# be_mdv.net
KiCad netlist of a schematic drawn in Altium Designer
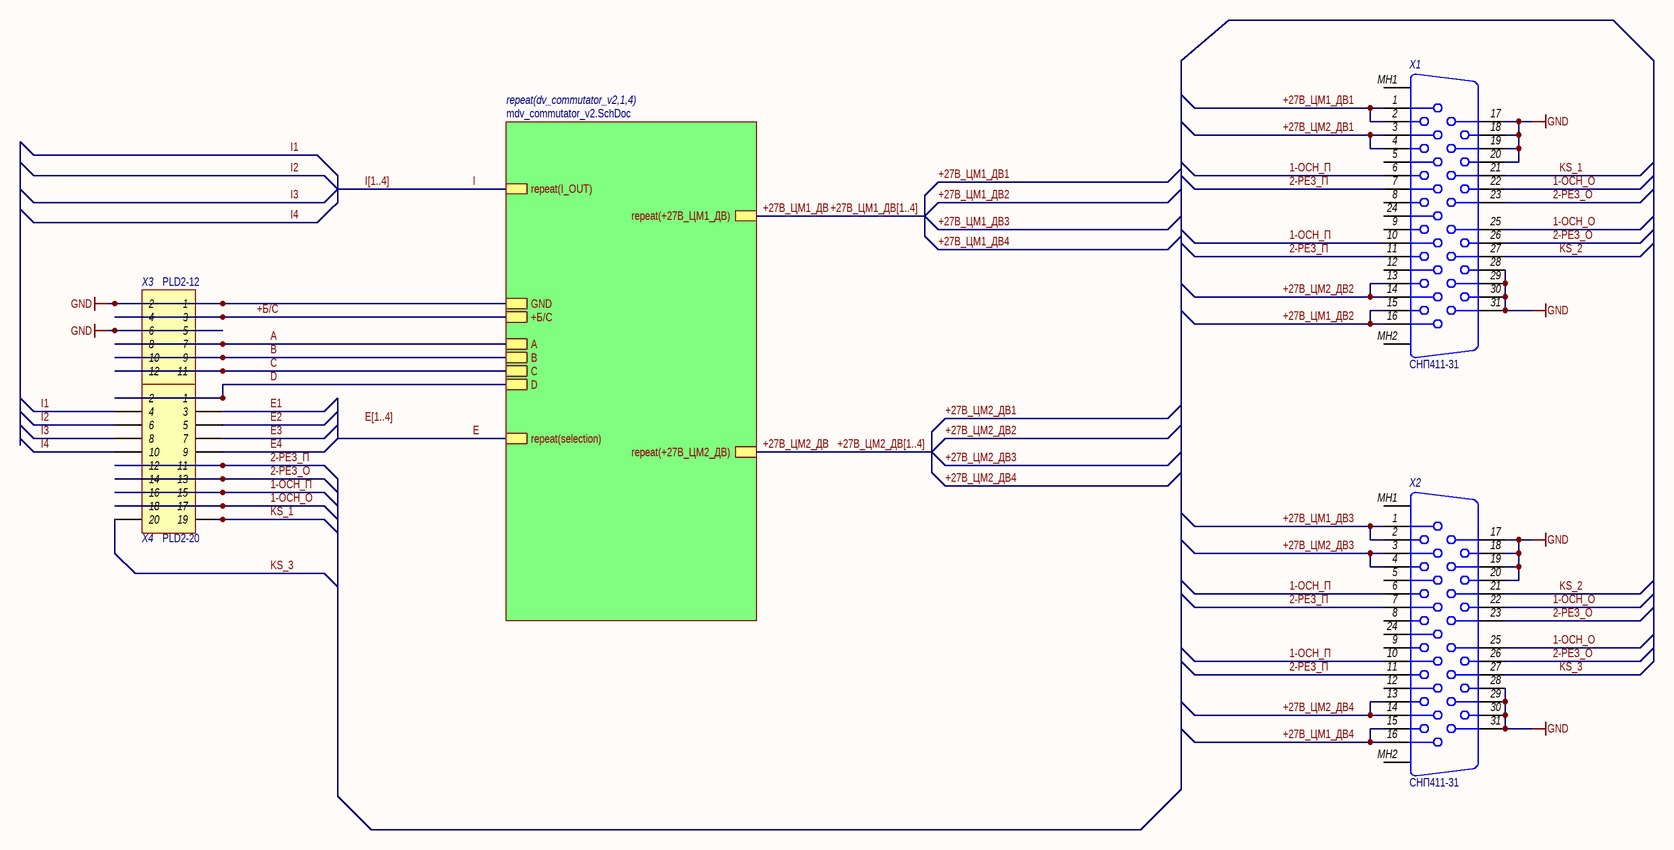
[diagram p0: be_mdv.SchDoc]

(export (version "E")
  (design (tool "Eeschema 10.0.6"))
  (components
    (comp (ref "X1")
      (value "SNP411-31")
      (footprint "SNP411-31")
      (description "СНП411-31, распиновка со стороны платы")
      (fields (field (name "НАИМЕНОВАНИЕ") "СНП411-31"))
      (libsource (lib "Connector") (part "СНП411-31"))
    )
    (comp (ref "X2")
      (value "SNP411-31")
      (footprint "SNP411-31")
      (description "СНП411-31, распиновка со стороны платы")
      (fields (field (name "НАИМЕНОВАНИЕ") "СНП411-31"))
      (libsource (lib "Connector") (part "СНП411-31"))
    )
    (comp (ref "X3")
      (value "Header 2X12")
      (footprint "PLD2-12")
      (description "Header, 12-Pin, Dual row")
      (fields (field (name "НАИМЕНОВАНИЕ") "PLD2-12"))
      (libsource (lib "Connector") (part "Header 2X12"))
    )
    (comp (ref "X4")
      (value "Header 2X20")
      (footprint "PLD2-20")
      (description "Header, 20-Pin, Dual row")
      (fields (field (name "НАИМЕНОВАНИЕ") "PLD2-20"))
      (libsource (lib "Connector") (part "Header 2X20"))
    )
  )
  (nets
    (net (code "2") (name "/+27В_ЦМ1_ДВ1") (class "Default")
      (node (ref "X1") (pin "1") (pinfunction "1_1") (pintype "passive"))
      (node (ref "X1") (pin "2") (pinfunction "2_2") (pintype "passive"))
    )
    (net (code "3") (name "/+27В_ЦМ1_ДВ2") (class "Default")
      (node (ref "X1") (pin "15") (pinfunction "15_15") (pintype "passive"))
      (node (ref "X1") (pin "16") (pinfunction "16_16") (pintype "passive"))
    )
    (net (code "4") (name "/+27В_ЦМ1_ДВ3") (class "Default")
      (node (ref "X2") (pin "1") (pinfunction "1_1") (pintype "passive"))
      (node (ref "X2") (pin "2") (pinfunction "2_2") (pintype "passive"))
    )
    (net (code "5") (name "/+27В_ЦМ1_ДВ4") (class "Default")
      (node (ref "X2") (pin "15") (pinfunction "15_15") (pintype "passive"))
      (node (ref "X2") (pin "16") (pinfunction "16_16") (pintype "passive"))
    )
    (net (code "7") (name "/+27В_ЦМ2_ДВ1") (class "Default")
      (node (ref "X1") (pin "3") (pinfunction "3_3") (pintype "passive"))
      (node (ref "X1") (pin "4") (pinfunction "4_4") (pintype "passive"))
    )
    (net (code "8") (name "/+27В_ЦМ2_ДВ2") (class "Default")
      (node (ref "X1") (pin "13") (pinfunction "13_13") (pintype "passive"))
      (node (ref "X1") (pin "14") (pinfunction "14_14") (pintype "passive"))
    )
    (net (code "9") (name "/+27В_ЦМ2_ДВ3") (class "Default")
      (node (ref "X2") (pin "3") (pinfunction "3_3") (pintype "passive"))
      (node (ref "X2") (pin "4") (pinfunction "4_4") (pintype "passive"))
    )
    (net (code "10") (name "/+27В_ЦМ2_ДВ4") (class "Default")
      (node (ref "X2") (pin "13") (pinfunction "13_13") (pintype "passive"))
      (node (ref "X2") (pin "14") (pinfunction "14_14") (pintype "passive"))
    )
    (net (code "11") (name "/+Б{slash}С") (class "Default")
      (node (ref "X3") (pin "3") (pinfunction "3_3") (pintype "passive"))
      (node (ref "X3") (pin "4") (pinfunction "4_4") (pintype "passive"))
    )
    (net (code "12") (name "/1-ОСН_О") (class "Default")
      (node (ref "X1") (pin "22") (pinfunction "22_22") (pintype "passive"))
      (node (ref "X1") (pin "25") (pinfunction "25_25") (pintype "passive"))
      (node (ref "X2") (pin "22") (pinfunction "22_22") (pintype "passive"))
      (node (ref "X2") (pin "25") (pinfunction "25_25") (pintype "passive"))
      (node (ref "X4") (pin "17") (pinfunction "17_17") (pintype "passive"))
      (node (ref "X4") (pin "18") (pinfunction "18_18") (pintype "passive"))
    )
    (net (code "13") (name "/1-ОСН_П") (class "Default")
      (node (ref "X1") (pin "10") (pinfunction "10_10") (pintype "passive"))
      (node (ref "X1") (pin "6") (pinfunction "6_6") (pintype "passive"))
      (node (ref "X2") (pin "10") (pinfunction "10_10") (pintype "passive"))
      (node (ref "X2") (pin "6") (pinfunction "6_6") (pintype "passive"))
      (node (ref "X4") (pin "15") (pinfunction "15_15") (pintype "passive"))
      (node (ref "X4") (pin "16") (pinfunction "16_16") (pintype "passive"))
    )
    (net (code "14") (name "/2-РЕЗ_О") (class "Default")
      (node (ref "X1") (pin "23") (pinfunction "23_23") (pintype "passive"))
      (node (ref "X1") (pin "26") (pinfunction "26_26") (pintype "passive"))
      (node (ref "X2") (pin "23") (pinfunction "23_23") (pintype "passive"))
      (node (ref "X2") (pin "26") (pinfunction "26_26") (pintype "passive"))
      (node (ref "X4") (pin "13") (pinfunction "13_13") (pintype "passive"))
      (node (ref "X4") (pin "14") (pinfunction "14_14") (pintype "passive"))
    )
    (net (code "15") (name "/2-РЕЗ_П") (class "Default")
      (node (ref "X1") (pin "11") (pinfunction "11_11") (pintype "passive"))
      (node (ref "X1") (pin "7") (pinfunction "7_7") (pintype "passive"))
      (node (ref "X2") (pin "11") (pinfunction "11_11") (pintype "passive"))
      (node (ref "X2") (pin "7") (pinfunction "7_7") (pintype "passive"))
      (node (ref "X4") (pin "11") (pinfunction "11_11") (pintype "passive"))
      (node (ref "X4") (pin "12") (pinfunction "12_12") (pintype "passive"))
    )
    (net (code "16") (name "/A") (class "Default")
      (node (ref "X3") (pin "7") (pinfunction "7_7") (pintype "passive"))
      (node (ref "X3") (pin "8") (pinfunction "8_8") (pintype "passive"))
    )
    (net (code "17") (name "/B") (class "Default")
      (node (ref "X3") (pin "10") (pinfunction "10_10") (pintype "passive"))
      (node (ref "X3") (pin "9") (pinfunction "9_9") (pintype "passive"))
    )
    (net (code "18") (name "/C") (class "Default")
      (node (ref "X3") (pin "11") (pinfunction "11_11") (pintype "passive"))
      (node (ref "X3") (pin "12") (pinfunction "12_12") (pintype "passive"))
    )
    (net (code "19") (name "/D") (class "Default")
      (node (ref "X4") (pin "1") (pinfunction "1_1") (pintype "passive"))
      (node (ref "X4") (pin "2") (pinfunction "2_2") (pintype "passive"))
    )
    (net (code "21") (name "/E1") (class "Default")
      (node (ref "X4") (pin "3") (pinfunction "3_3") (pintype "passive"))
    )
    (net (code "22") (name "/E2") (class "Default")
      (node (ref "X4") (pin "5") (pinfunction "5_5") (pintype "passive"))
    )
    (net (code "23") (name "/E3") (class "Default")
      (node (ref "X4") (pin "7") (pinfunction "7_7") (pintype "passive"))
    )
    (net (code "24") (name "/E4") (class "Default")
      (node (ref "X4") (pin "9") (pinfunction "9_9") (pintype "passive"))
    )
    (net (code "27") (name "/I1") (class "Default")
      (node (ref "X4") (pin "4") (pinfunction "4_4") (pintype "passive"))
    )
    (net (code "28") (name "/I2") (class "Default")
      (node (ref "X4") (pin "6") (pinfunction "6_6") (pintype "passive"))
    )
    (net (code "29") (name "/I3") (class "Default")
      (node (ref "X4") (pin "8") (pinfunction "8_8") (pintype "passive"))
    )
    (net (code "30") (name "/I4") (class "Default")
      (node (ref "X4") (pin "10") (pinfunction "10_10") (pintype "passive"))
    )
    (net (code "32") (name "/KS_1") (class "Default")
      (node (ref "X1") (pin "21") (pinfunction "21_21") (pintype "passive"))
      (node (ref "X4") (pin "19") (pinfunction "19_19") (pintype "passive"))
    )
    (net (code "33") (name "/KS_2") (class "Default")
      (node (ref "X1") (pin "27") (pinfunction "27_27") (pintype "passive"))
      (node (ref "X2") (pin "21") (pinfunction "21_21") (pintype "passive"))
    )
    (net (code "34") (name "/KS_3") (class "Default")
      (node (ref "X2") (pin "27") (pinfunction "27_27") (pintype "passive"))
      (node (ref "X4") (pin "20") (pinfunction "20_20") (pintype "passive"))
    )
    (net (code "35") (name "GND") (class "Default")
      (node (ref "X1") (pin "17") (pinfunction "17_17") (pintype "passive"))
      (node (ref "X1") (pin "18") (pinfunction "189_18") (pintype "passive"))
      (node (ref "X1") (pin "19") (pinfunction "19_19") (pintype "passive"))
      (node (ref "X1") (pin "20") (pinfunction "20_20") (pintype "passive"))
      (node (ref "X1") (pin "28") (pinfunction "28_28") (pintype "passive"))
      (node (ref "X1") (pin "29") (pinfunction "29_29") (pintype "passive"))
      (node (ref "X1") (pin "30") (pinfunction "30_30") (pintype "passive"))
      (node (ref "X1") (pin "31") (pinfunction "31_31") (pintype "passive"))
      (node (ref "X2") (pin "17") (pinfunction "17_17") (pintype "passive"))
      (node (ref "X2") (pin "18") (pinfunction "189_18") (pintype "passive"))
      (node (ref "X2") (pin "19") (pinfunction "19_19") (pintype "passive"))
      (node (ref "X2") (pin "20") (pinfunction "20_20") (pintype "passive"))
      (node (ref "X2") (pin "28") (pinfunction "28_28") (pintype "passive"))
      (node (ref "X2") (pin "29") (pinfunction "29_29") (pintype "passive"))
      (node (ref "X2") (pin "30") (pinfunction "30_30") (pintype "passive"))
      (node (ref "X2") (pin "31") (pinfunction "31_31") (pintype "passive"))
      (node (ref "X3") (pin "1") (pinfunction "1_1") (pintype "passive"))
      (node (ref "X3") (pin "2") (pinfunction "2_2") (pintype "passive"))
      (node (ref "X3") (pin "5") (pinfunction "5_5") (pintype "passive"))
      (node (ref "X3") (pin "6") (pinfunction "6_6") (pintype "passive"))
    )
    (net (code "36") (name "unconnected-(X1-Pad5)") (class "Default")
      (node (ref "X1") (pin "5") (pinfunction "5_5") (pintype "passive"))
    )
    (net (code "37") (name "unconnected-(X1-Pad8)") (class "Default")
      (node (ref "X1") (pin "8") (pinfunction "8_8") (pintype "passive"))
    )
    (net (code "38") (name "unconnected-(X1-Pad9)") (class "Default")
      (node (ref "X1") (pin "9") (pinfunction "9_9") (pintype "passive"))
    )
    (net (code "39") (name "unconnected-(X1-Pad12)") (class "Default")
      (node (ref "X1") (pin "12") (pinfunction "12_12") (pintype "passive"))
    )
    (net (code "40") (name "unconnected-(X1-Pad24)") (class "Default")
      (node (ref "X1") (pin "24") (pinfunction "24_24") (pintype "passive"))
    )
    (net (code "41") (name "unconnected-(X1-PadMH1)") (class "Default")
      (node (ref "X1") (pin "MH1") (pinfunction "MH1_MH1") (pintype "passive"))
    )
    (net (code "42") (name "unconnected-(X1-PadMH2)") (class "Default")
      (node (ref "X1") (pin "MH2") (pinfunction "MH2_MH2") (pintype "passive"))
    )
    (net (code "43") (name "unconnected-(X2-Pad5)") (class "Default")
      (node (ref "X2") (pin "5") (pinfunction "5_5") (pintype "passive"))
    )
    (net (code "44") (name "unconnected-(X2-Pad8)") (class "Default")
      (node (ref "X2") (pin "8") (pinfunction "8_8") (pintype "passive"))
    )
    (net (code "45") (name "unconnected-(X2-Pad9)") (class "Default")
      (node (ref "X2") (pin "9") (pinfunction "9_9") (pintype "passive"))
    )
    (net (code "46") (name "unconnected-(X2-Pad12)") (class "Default")
      (node (ref "X2") (pin "12") (pinfunction "12_12") (pintype "passive"))
    )
    (net (code "47") (name "unconnected-(X2-Pad24)") (class "Default")
      (node (ref "X2") (pin "24") (pinfunction "24_24") (pintype "passive"))
    )
    (net (code "48") (name "unconnected-(X2-PadMH1)") (class "Default")
      (node (ref "X2") (pin "MH1") (pinfunction "MH1_MH1") (pintype "passive"))
    )
    (net (code "49") (name "unconnected-(X2-PadMH2)") (class "Default")
      (node (ref "X2") (pin "MH2") (pinfunction "MH2_MH2") (pintype "passive"))
    )
  )
)
